# Power_Supply.net
KiCad netlist of a schematic drawn in Altium Designer
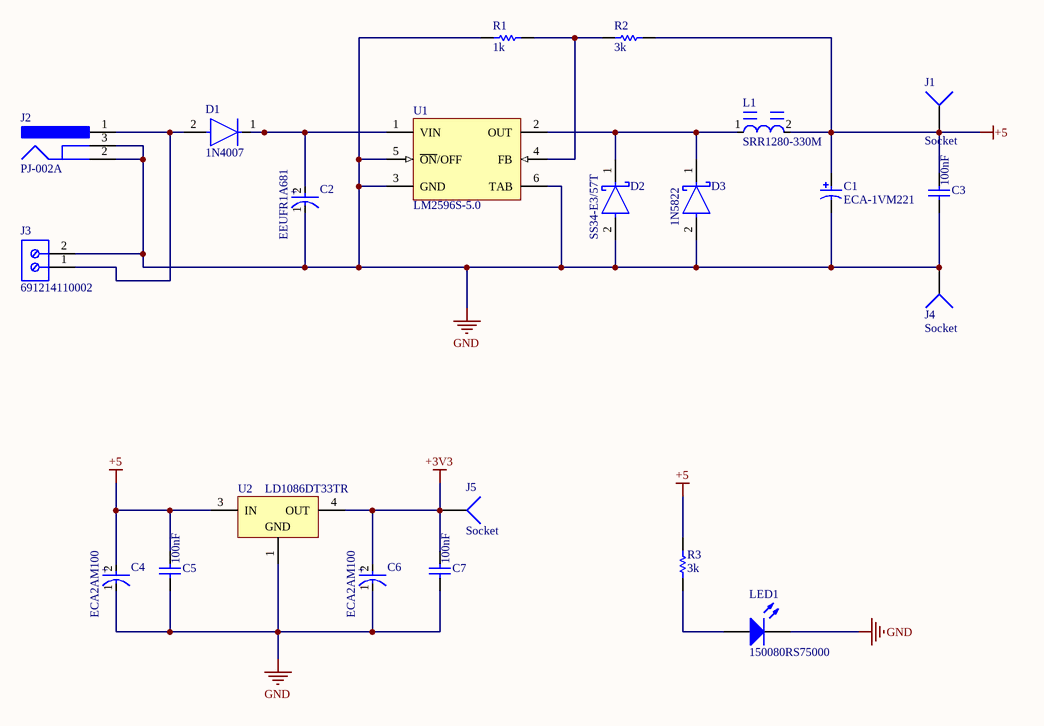
[diagram p0: Power_Supply.SchDoc]

(export (version "E")
  (design (tool "Eeschema 10.0.6"))
  (components
    (comp (ref "C1")
      (value "ECA-1VM221")
      (footprint "PNSC-ECA-1VM221-2")
      (description "Aluminum Electrolytic Capacitor, 220 uF, +/- 20%, 35 V, -40 to 85 degC, 2-Pin THD, RoHS, Bulk")
      (fields (field (name "MANUFACTURER") "Panasonic"))
      (libsource (lib "Altium Content Vault") (part "CAP-P-2"))
    )
    (comp (ref "C2")
      (value "EEUFR1A681")
      (footprint "FP-RAD-TH-D_8_0_5-L_11_5-MFG")
      (description "Aluminum Electrolytic Capacitors (Radial Lead Type) 680uF ±20% 10V")
      (fields (field (name "TOLERANCE") "20%") (field (name "VOLTAGE") "10V"))
      (libsource (lib "Altium Content Vault") (part "a00bbbee19879c290e62620ae7e47b1"))
    )
    (comp (ref "C3")
      (value "100nF")
      (footprint "CAPC2013X135X45LL10T25")
      (fields (field (name "MANUFACTURER") "Murata") (field (name "PART NUMBER") "GRM21BR71H105KA12L"))
      (libsource (lib "Altium Content Vault") (part "CAP"))
    )
    (comp (ref "C4")
      (value "ECA2AM100")
      (footprint "FP-RAD-TH-D_5_0_5-L_11_1-MFG")
      (description "Aluminum Electrolytic Capacitors (Radial Lead Type) 10uF ±20% 100V")
      (fields (field (name "VOLTAGE") "100V") (field (name "TOLERANCE") "20%"))
      (libsource (lib "Altium Content Vault") (part "a00bbbee19879c290e62620ae7e47b1"))
    )
    (comp (ref "C5")
      (value "100nF")
      (footprint "CAPC2013X135X45LL10T25")
      (fields (field (name "MANUFACTURER") "Murata") (field (name "PART NUMBER") "GRM21BR71H105KA12L"))
      (libsource (lib "Altium Content Vault") (part "CAP"))
    )
    (comp (ref "C6")
      (value "ECA2AM100")
      (footprint "FP-RAD-TH-D_5_0_5-L_11_1-MFG")
      (description "Aluminum Electrolytic Capacitors (Radial Lead Type) 10uF ±20% 100V")
      (fields (field (name "VOLTAGE") "100V") (field (name "TOLERANCE") "20%"))
      (libsource (lib "Altium Content Vault") (part "a00bbbee19879c290e62620ae7e47b1"))
    )
    (comp (ref "C7")
      (value "100nF")
      (footprint "CAPC2013X135X45LL10T25")
      (fields (field (name "MANUFACTURER") "Murata") (field (name "PART NUMBER") "GRM21BR71H105KA12L"))
      (libsource (lib "Altium Content Vault") (part "CAP"))
    )
    (comp (ref "D1")
      (value "1N4007")
      (footprint "FP-1N4007-MFG")
      (description "Rectifier diode 1000 V 1 A DO-41, ,")
      (fields
        (field (name "MANUFACTURER") "Diotec")
        (field (name "OCTOPART") "https://octopart.com/1n4007-diotec-4040411")
      )
      (libsource (lib "Altium Content Vault") (part "d7152d700b627762746794eb795d46e"))
    )
    (comp (ref "D2")
      (value "SS34-E3/57T")
      (footprint "FP-95402-MFG")
      (description "DIODE SCHOTTKY 40V 3A DO214AB")
      (fields
        (field (name "MANUFACTURER") "Vishay")
        (field (name "OCTOPART") "https://octopart.com/ss34-e3%2F57t-vishay-39552907")
      )
      (libsource (lib "Altium Content Vault") (part "1d6ec82d83fb6aee721767c19dac4b9"))
    )
    (comp (ref "D3")
      (value "1N5822")
      (footprint "FP-DO-201AD-MFG")
      (description "DIODE SCHOTTKY 40V 3A DO201AD")
      (fields
        (field (name "OCTOPART") "https://octopart.com/1n5822-stmicroelectronics-323225")
        (field (name "MANUFACTURER") "STMicroelectronics")
      )
      (libsource (lib "Altium Content Vault") (part "1d6ec82d83fb6aee721767c19dac4b9"))
    )
    (comp (ref "J1")
      (value "Socket")
      (footprint "PIN1")
      (fields (field (name "PUBLISHER") "Altium Limited"))
      (libsource (lib "Miscellaneous Connectors") (part "Socket"))
    )
    (comp (ref "J2")
      (value "PJ-002A")
      (footprint "CUI-PJ-002A_V")
      (fields (field (name "MANUFACTURER") "CUIInc."))
      (libsource (lib "Altium Content Vault") (part "JACK-2CD3-RN_B"))
    )
    (comp (ref "J3")
      (value "691214110002")
      (footprint "691214110002")
      (description "Serie 2141 - 3.50 mm Horizontal Entry Modular with Rising Cage Clamp WR-TBL, 2 pin")
      (fields (field (name "MANUFACTURER") "Wurth Elektronik") (field (name "PUBLISHER") "WurthElektronik"))
      (libsource (lib "Altium Content Vault") (part "WE-CN-1P-F-TB2"))
    )
    (comp (ref "J4")
      (value "Socket")
      (footprint "PIN1")
      (fields (field (name "PUBLISHER") "Altium Limited"))
      (libsource (lib "Miscellaneous Connectors") (part "Socket"))
    )
    (comp (ref "J5")
      (value "Socket")
      (footprint "PIN1")
      (fields (field (name "PUBLISHER") "Altium Limited"))
      (libsource (lib "Miscellaneous Connectors") (part "Socket"))
    )
    (comp (ref "L1")
      (value "SRR1280-330M")
      (footprint "FP-SRR1280-MFG")
      (description "FIXED IND 33UH 3.5A 57 MOHM SMD")
      (fields (field (name "TOLERANCE") "20%"))
      (libsource (lib "Altium Content Vault") (part "6d0fbef048cab01dc475e6ab11ab505"))
    )
    (comp (ref "LED1")
      (value "150080RS75000")
      (footprint "0805_A")
      (description "SMD mono-color Chip LED, WL-SMCW, Red")
      (fields (field (name "MANUFACTURER") "Wuerth Elektronik"))
      (libsource (lib "Altium Content Vault") (part "WE-LED_K1A2-2"))
    )
    (comp (ref "R1")
      (value "1k")
      (footprint "RESC2013X70X40NL20T20")
      (fields (field (name "PART NUMBER") "ERJ6ENF47R0V") (field (name "MANUFACTURER") "Panasonic"))
      (libsource (lib "Altium Content Vault") (part "RES"))
    )
    (comp (ref "R2")
      (value "3k")
      (footprint "RESC2013X70X40NL20T20")
      (fields (field (name "PART NUMBER") "ERJ6ENF47R0V") (field (name "MANUFACTURER") "Panasonic"))
      (libsource (lib "Altium Content Vault") (part "RES"))
    )
    (comp (ref "R3")
      (value "3k")
      (footprint "RESC2013X70X40NL20T20")
      (fields (field (name "PART NUMBER") "ERJ6ENF47R0V") (field (name "MANUFACTURER") "Panasonic"))
      (libsource (lib "Altium Content Vault") (part "RES"))
    )
    (comp (ref "U1")
      (value "LM2596S-5.0")
      (footprint "KTT0005B_L")
      (description "SIMPLE SWITCHER® Power Converter 150 KHz 3A Step-Down Voltage Regulator, 5-pin TO-263")
      (fields (field (name "MANUFACTURER") "Texas Instruments"))
      (libsource (lib "Altium Content Vault") (part "PM-REG-LM2575HVS-12"))
    )
    (comp (ref "U2")
      (value "LD1086DT33TR")
      (footprint "TO-252_L")
      (description "1.5A, Low Drop Positive Voltage Regulator, 3.3V, 3-Pin DPAK, Tape and Reel")
      (libsource (lib "Altium Content Vault") (part "PM-REG-LD1085-SOT3"))
    )
  )
  (nets
    (net (code "1") (name "+3V3") (class "Default")
      (node (ref "C6") (pin "2") (pinfunction "A_2") (pintype "passive"))
      (node (ref "C7") (pin "2") (pinfunction "2_2") (pintype "passive"))
      (node (ref "J5") (pin "1") (pinfunction "1_1") (pintype "passive"))
      (node (ref "U2") (pin "4") (pinfunction "OUT_4") (pintype "power_in"))
    )
    (net (code "2") (name "+5") (class "Default")
      (node (ref "C1") (pin "1") (pinfunction "1_1") (pintype "passive"))
      (node (ref "C3") (pin "2") (pinfunction "2_2") (pintype "passive"))
      (node (ref "C4") (pin "2") (pinfunction "A_2") (pintype "passive"))
      (node (ref "C5") (pin "2") (pinfunction "2_2") (pintype "passive"))
      (node (ref "J1") (pin "1") (pinfunction "1_1") (pintype "passive"))
      (node (ref "L1") (pin "2") (pinfunction "2_2") (pintype "passive"))
      (node (ref "R2") (pin "2") (pinfunction "2_2") (pintype "passive"))
      (node (ref "R3") (pin "2") (pinfunction "2_2") (pintype "passive"))
      (node (ref "U2") (pin "3") (pinfunction "IN_3") (pintype "power_in"))
    )
    (net (code "3") (name "GND") (class "Default")
      (node (ref "C1") (pin "2") (pinfunction "2_2") (pintype "passive"))
      (node (ref "C2") (pin "1") (pinfunction "C_1") (pintype "passive"))
      (node (ref "C3") (pin "1") (pinfunction "1_1") (pintype "passive"))
      (node (ref "C4") (pin "1") (pinfunction "C_1") (pintype "passive"))
      (node (ref "C5") (pin "1") (pinfunction "1_1") (pintype "passive"))
      (node (ref "C6") (pin "1") (pinfunction "C_1") (pintype "passive"))
      (node (ref "C7") (pin "1") (pinfunction "1_1") (pintype "passive"))
      (node (ref "D2") (pin "2") (pinfunction "A_2") (pintype "passive"))
      (node (ref "D3") (pin "2") (pinfunction "A_2") (pintype "passive"))
      (node (ref "J2") (pin "2") (pinfunction "2_2") (pintype "passive"))
      (node (ref "J2") (pin "3") (pinfunction "3_3") (pintype "passive"))
      (node (ref "J3") (pin "2") (pinfunction "2_2") (pintype "passive"))
      (node (ref "J4") (pin "1") (pinfunction "1_1") (pintype "passive"))
      (node (ref "LED1") (pin "1") (pinfunction "K_1") (pintype "passive"))
      (node (ref "R1") (pin "1") (pinfunction "1_1") (pintype "passive"))
      (node (ref "U1") (pin "3") (pinfunction "GND_3") (pintype "power_in"))
      (node (ref "U1") (pin "5") (pinfunction "~{ON}/OFF_5") (pintype "input"))
      (node (ref "U1") (pin "6") (pinfunction "TAB_6") (pintype "power_in"))
      (node (ref "U2") (pin "1") (pinfunction "GND_1") (pintype "power_in"))
    )
    (net (code "4") (name "Net-(C2-A)") (class "Default")
      (node (ref "C2") (pin "2") (pinfunction "A_2") (pintype "passive"))
      (node (ref "D1") (pin "1") (pinfunction "C_1") (pintype "passive"))
      (node (ref "U1") (pin "1") (pinfunction "VIN_1") (pintype "power_in"))
    )
    (net (code "5") (name "Net-(D1-A)") (class "Default")
      (node (ref "D1") (pin "2") (pinfunction "A_2") (pintype "passive"))
      (node (ref "J2") (pin "1") (pinfunction "1_1") (pintype "passive"))
      (node (ref "J3") (pin "1") (pinfunction "1_1") (pintype "passive"))
    )
    (net (code "6") (name "Net-(D2-C)") (class "Default")
      (node (ref "D2") (pin "1") (pinfunction "C_1") (pintype "passive"))
      (node (ref "D3") (pin "1") (pinfunction "C_1") (pintype "passive"))
      (node (ref "L1") (pin "1") (pinfunction "1_1") (pintype "passive"))
      (node (ref "U1") (pin "2") (pinfunction "OUT_2") (pintype "power_in"))
    )
    (net (code "7") (name "Net-(LED1-A)") (class "Default")
      (node (ref "LED1") (pin "2") (pinfunction "A_2") (pintype "passive"))
      (node (ref "R3") (pin "1") (pinfunction "1_1") (pintype "passive"))
    )
    (net (code "8") (name "Net-(U1-FB)") (class "Default")
      (node (ref "R1") (pin "2") (pinfunction "2_2") (pintype "passive"))
      (node (ref "R2") (pin "1") (pinfunction "1_1") (pintype "passive"))
      (node (ref "U1") (pin "4") (pinfunction "FB_4") (pintype "input"))
    )
  )
)
